# Heatsink_Testboard.net
KiCad netlist of a schematic drawn in EAGLE
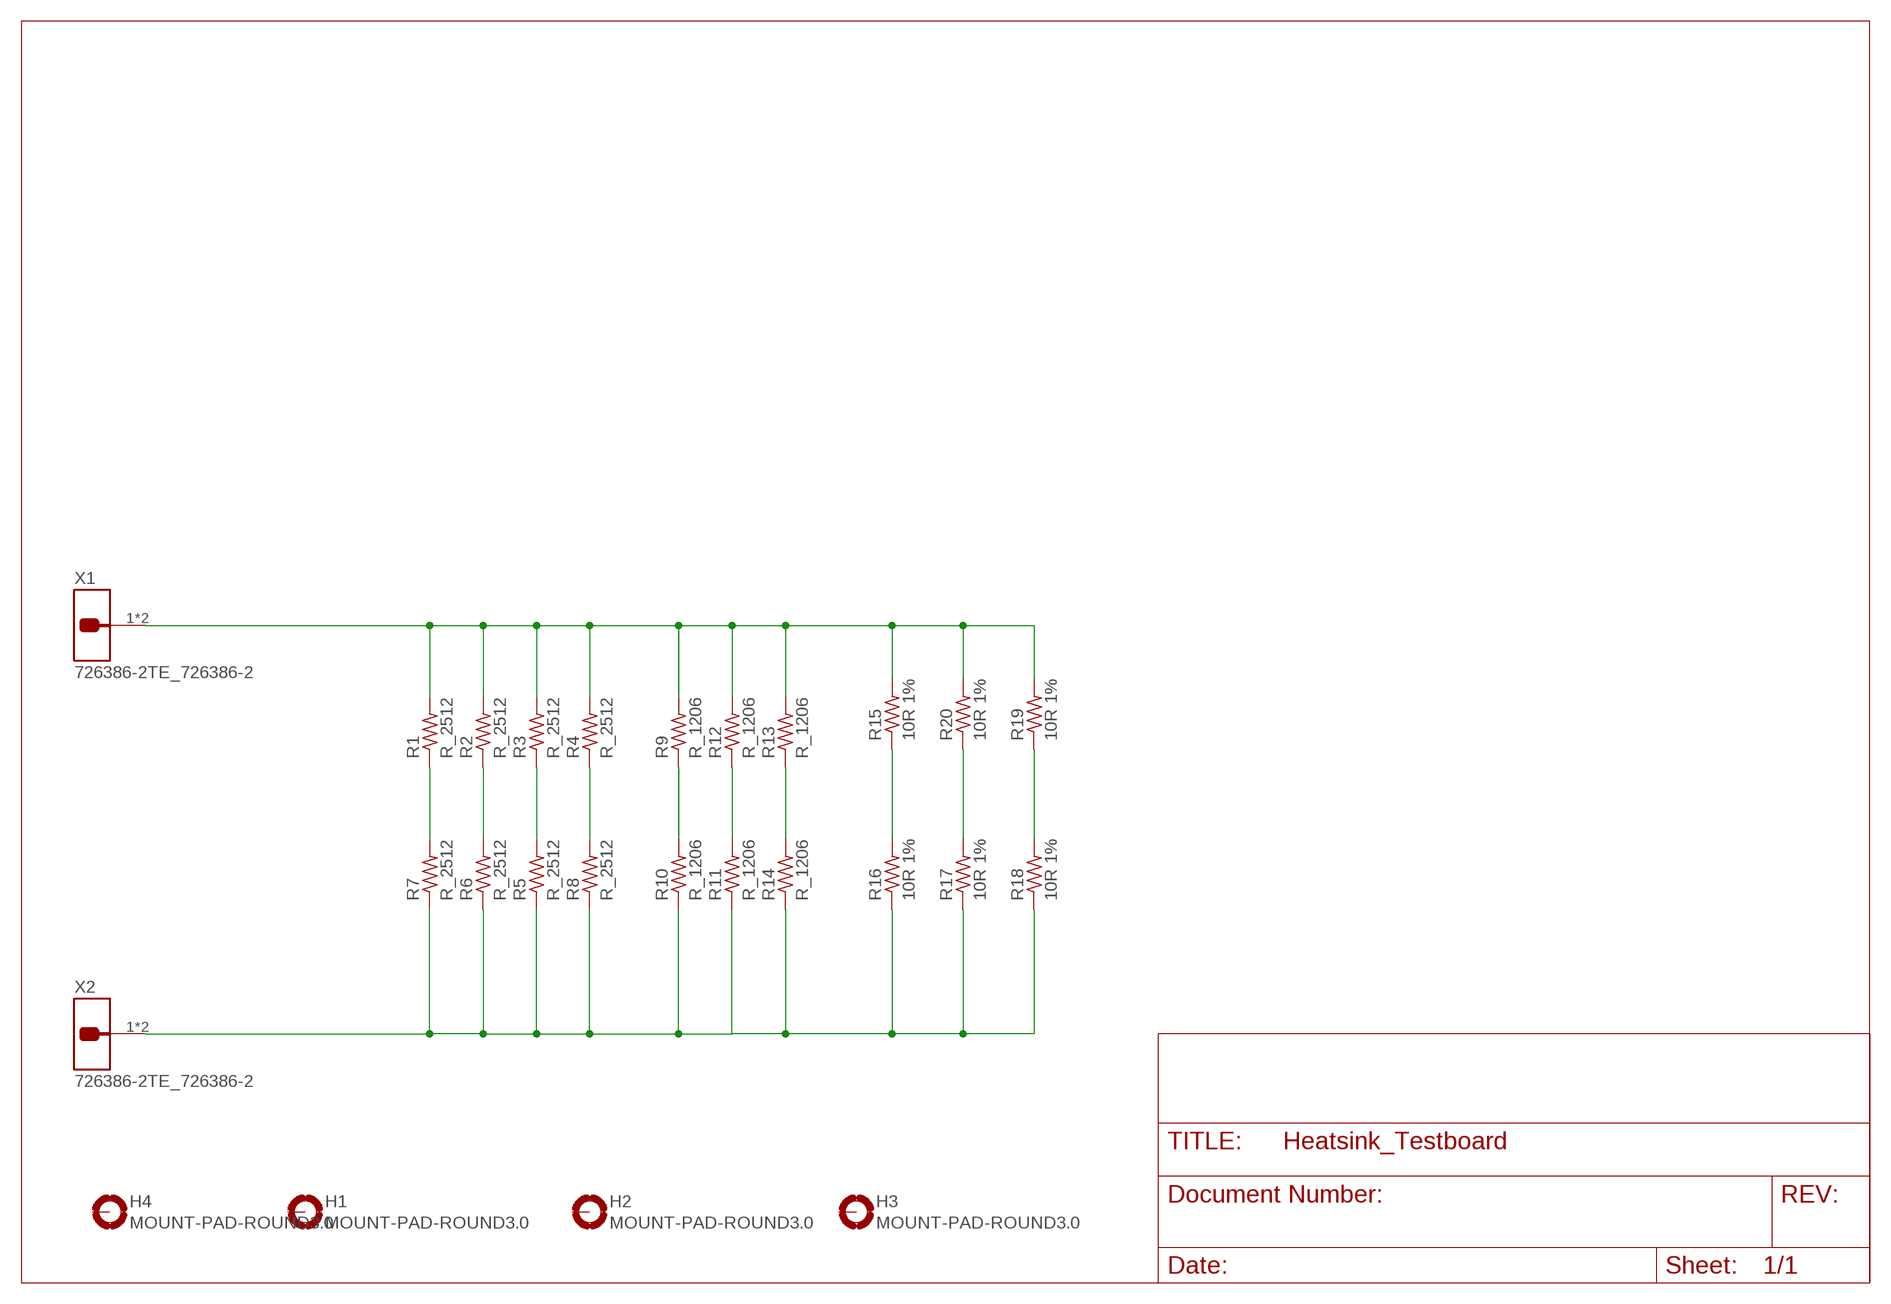
[diagram p0: schematic, sheet 1]

(export (version "E")
  (design (tool "Eeschema 10.0.6"))
  (components
    (comp (ref "H1")
      (value "MOUNT-PAD-ROUND3.0")
      (footprint "eagle-import:3,0-PAD")
      (libsource (lib "eagle-import") (part "MOUNT-PAD-ROUND3.0"))
    )
    (comp (ref "H2")
      (value "MOUNT-PAD-ROUND3.0")
      (footprint "eagle-import:3,0-PAD")
      (libsource (lib "eagle-import") (part "MOUNT-PAD-ROUND3.0"))
    )
    (comp (ref "H3")
      (value "MOUNT-PAD-ROUND3.0")
      (footprint "eagle-import:3,0-PAD")
      (libsource (lib "eagle-import") (part "MOUNT-PAD-ROUND3.0"))
    )
    (comp (ref "H4")
      (value "MOUNT-PAD-ROUND3.0")
      (footprint "eagle-import:3,0-PAD")
      (libsource (lib "eagle-import") (part "MOUNT-PAD-ROUND3.0"))
    )
    (comp (ref "R1")
      (value "R_2512")
      (footprint "eagle-import:EIA2512")
      (libsource (lib "eagle-import") (part "R_2512"))
    )
    (comp (ref "R2")
      (value "R_2512")
      (footprint "eagle-import:EIA2512")
      (libsource (lib "eagle-import") (part "R_2512"))
    )
    (comp (ref "R3")
      (value "R_2512")
      (footprint "eagle-import:EIA2512")
      (libsource (lib "eagle-import") (part "R_2512"))
    )
    (comp (ref "R4")
      (value "R_2512")
      (footprint "eagle-import:EIA2512")
      (libsource (lib "eagle-import") (part "R_2512"))
    )
    (comp (ref "R5")
      (value "R_2512")
      (footprint "eagle-import:EIA2512")
      (libsource (lib "eagle-import") (part "R_2512"))
    )
    (comp (ref "R6")
      (value "R_2512")
      (footprint "eagle-import:EIA2512")
      (libsource (lib "eagle-import") (part "R_2512"))
    )
    (comp (ref "R7")
      (value "R_2512")
      (footprint "eagle-import:EIA2512")
      (libsource (lib "eagle-import") (part "R_2512"))
    )
    (comp (ref "R8")
      (value "R_2512")
      (footprint "eagle-import:EIA2512")
      (libsource (lib "eagle-import") (part "R_2512"))
    )
    (comp (ref "R9")
      (value "R_1206")
      (footprint "eagle-import:R1206")
      (libsource (lib "eagle-import") (part "R_1206"))
    )
    (comp (ref "R10")
      (value "R_1206")
      (footprint "eagle-import:R1206")
      (libsource (lib "eagle-import") (part "R_1206"))
    )
    (comp (ref "R11")
      (value "R_1206")
      (footprint "eagle-import:R1206")
      (libsource (lib "eagle-import") (part "R_1206"))
    )
    (comp (ref "R12")
      (value "R_1206")
      (footprint "eagle-import:R1206")
      (libsource (lib "eagle-import") (part "R_1206"))
    )
    (comp (ref "R13")
      (value "R_1206")
      (footprint "eagle-import:R1206")
      (libsource (lib "eagle-import") (part "R_1206"))
    )
    (comp (ref "R14")
      (value "R_1206")
      (footprint "eagle-import:R1206")
      (libsource (lib "eagle-import") (part "R_1206"))
    )
    (comp (ref "R15")
      (value "10R 1%")
      (footprint "eagle-import:EIA0603")
      (libsource (lib "eagle-import") (part "R_0603"))
    )
    (comp (ref "R16")
      (value "10R 1%")
      (footprint "eagle-import:EIA0603")
      (libsource (lib "eagle-import") (part "R_0603"))
    )
    (comp (ref "R17")
      (value "10R 1%")
      (footprint "eagle-import:EIA0603")
      (libsource (lib "eagle-import") (part "R_0603"))
    )
    (comp (ref "R18")
      (value "10R 1%")
      (footprint "eagle-import:EIA0603")
      (libsource (lib "eagle-import") (part "R_0603"))
    )
    (comp (ref "R19")
      (value "10R 1%")
      (footprint "eagle-import:EIA0603")
      (libsource (lib "eagle-import") (part "R_0603"))
    )
    (comp (ref "R20")
      (value "10R 1%")
      (footprint "eagle-import:EIA0603")
      (libsource (lib "eagle-import") (part "R_0603"))
    )
    (comp (ref "X1")
      (value "726386-2TE_726386-2")
      (footprint "eagle-import:TE_726386-2")
      (fields
        (field (name "DIGIKEY_PART_NUMBER") "A114371-ND")
        (field (name "MF") "TE")
        (field (name "MOUSER_PART_NUMBER") "571-726386-2")
      )
      (libsource (lib "eagle-import") (part "726386-2TE_726386-2"))
    )
    (comp (ref "X2")
      (value "726386-2TE_726386-2")
      (footprint "eagle-import:TE_726386-2")
      (fields
        (field (name "DIGIKEY_PART_NUMBER") "A114371-ND")
        (field (name "MF") "TE")
        (field (name "MOUSER_PART_NUMBER") "571-726386-2")
      )
      (libsource (lib "eagle-import") (part "726386-2TE_726386-2"))
    )
  )
  (nets
    (net (code "1") (name "Net-(R1-Pad1)") (class "Default")
      (node (ref "R1") (pin "1") (pinfunction "1_1") (pintype "passive"))
      (node (ref "R7") (pin "2") (pinfunction "2_2") (pintype "passive"))
    )
    (net (code "2") (name "Net-(R1-Pad2)") (class "Default")
      (node (ref "R1") (pin "2") (pinfunction "2_2") (pintype "passive"))
      (node (ref "R12") (pin "2") (pinfunction "2_2") (pintype "passive"))
      (node (ref "R13") (pin "2") (pinfunction "2_2") (pintype "passive"))
      (node (ref "R15") (pin "2") (pinfunction "2_2") (pintype "passive"))
      (node (ref "R19") (pin "2") (pinfunction "2_2") (pintype "passive"))
      (node (ref "R2") (pin "2") (pinfunction "2_2") (pintype "passive"))
      (node (ref "R20") (pin "2") (pinfunction "2_2") (pintype "passive"))
      (node (ref "R3") (pin "2") (pinfunction "2_2") (pintype "passive"))
      (node (ref "R4") (pin "2") (pinfunction "2_2") (pintype "passive"))
      (node (ref "R9") (pin "2") (pinfunction "2_2") (pintype "passive"))
      (node (ref "X1") (pin "1") (pinfunction "1_1") (pintype "passive"))
      (node (ref "X1") (pin "1-2") (pinfunction "1_1-2") (pintype "passive"))
    )
    (net (code "3") (name "Net-(R2-Pad1)") (class "Default")
      (node (ref "R2") (pin "1") (pinfunction "1_1") (pintype "passive"))
      (node (ref "R6") (pin "2") (pinfunction "2_2") (pintype "passive"))
    )
    (net (code "4") (name "Net-(R3-Pad1)") (class "Default")
      (node (ref "R3") (pin "1") (pinfunction "1_1") (pintype "passive"))
      (node (ref "R5") (pin "2") (pinfunction "2_2") (pintype "passive"))
    )
    (net (code "5") (name "Net-(R4-Pad1)") (class "Default")
      (node (ref "R4") (pin "1") (pinfunction "1_1") (pintype "passive"))
      (node (ref "R8") (pin "2") (pinfunction "2_2") (pintype "passive"))
    )
    (net (code "6") (name "Net-(R10-Pad1)") (class "Default")
      (node (ref "R10") (pin "1") (pinfunction "1_1") (pintype "passive"))
      (node (ref "R11") (pin "1") (pinfunction "1_1") (pintype "passive"))
      (node (ref "R14") (pin "1") (pinfunction "1_1") (pintype "passive"))
      (node (ref "R16") (pin "1") (pinfunction "1_1") (pintype "passive"))
      (node (ref "R17") (pin "1") (pinfunction "1_1") (pintype "passive"))
      (node (ref "R18") (pin "1") (pinfunction "1_1") (pintype "passive"))
      (node (ref "R5") (pin "1") (pinfunction "1_1") (pintype "passive"))
      (node (ref "R6") (pin "1") (pinfunction "1_1") (pintype "passive"))
      (node (ref "R7") (pin "1") (pinfunction "1_1") (pintype "passive"))
      (node (ref "R8") (pin "1") (pinfunction "1_1") (pintype "passive"))
      (node (ref "X2") (pin "1") (pinfunction "1_1") (pintype "passive"))
      (node (ref "X2") (pin "1-2") (pinfunction "1_1-2") (pintype "passive"))
    )
    (net (code "7") (name "Net-(R10-Pad2)") (class "Default")
      (node (ref "R10") (pin "2") (pinfunction "2_2") (pintype "passive"))
      (node (ref "R9") (pin "1") (pinfunction "1_1") (pintype "passive"))
    )
    (net (code "8") (name "Net-(R11-Pad2)") (class "Default")
      (node (ref "R11") (pin "2") (pinfunction "2_2") (pintype "passive"))
      (node (ref "R12") (pin "1") (pinfunction "1_1") (pintype "passive"))
    )
    (net (code "9") (name "Net-(R13-Pad1)") (class "Default")
      (node (ref "R13") (pin "1") (pinfunction "1_1") (pintype "passive"))
      (node (ref "R14") (pin "2") (pinfunction "2_2") (pintype "passive"))
    )
    (net (code "10") (name "Net-(R15-Pad1)") (class "Default")
      (node (ref "R15") (pin "1") (pinfunction "1_1") (pintype "passive"))
      (node (ref "R16") (pin "2") (pinfunction "2_2") (pintype "passive"))
    )
    (net (code "11") (name "Net-(R17-Pad2)") (class "Default")
      (node (ref "R17") (pin "2") (pinfunction "2_2") (pintype "passive"))
      (node (ref "R20") (pin "1") (pinfunction "1_1") (pintype "passive"))
    )
    (net (code "12") (name "Net-(R18-Pad2)") (class "Default")
      (node (ref "R18") (pin "2") (pinfunction "2_2") (pintype "passive"))
      (node (ref "R19") (pin "1") (pinfunction "1_1") (pintype "passive"))
    )
    (net (code "13") (name "unconnected-(H1-MOUNT-PadB3,0)") (class "Default")
      (node (ref "H1") (pin "B3,0") (pinfunction "MOUNT_B3,0") (pintype "passive"))
    )
    (net (code "14") (name "unconnected-(H2-MOUNT-PadB3,0)") (class "Default")
      (node (ref "H2") (pin "B3,0") (pinfunction "MOUNT_B3,0") (pintype "passive"))
    )
    (net (code "15") (name "unconnected-(H3-MOUNT-PadB3,0)") (class "Default")
      (node (ref "H3") (pin "B3,0") (pinfunction "MOUNT_B3,0") (pintype "passive"))
    )
    (net (code "16") (name "unconnected-(H4-MOUNT-PadB3,0)") (class "Default")
      (node (ref "H4") (pin "B3,0") (pinfunction "MOUNT_B3,0") (pintype "passive"))
    )
  )
)
